# VM_Motor_v2_3.net
KiCad netlist of a schematic drawn in EAGLE
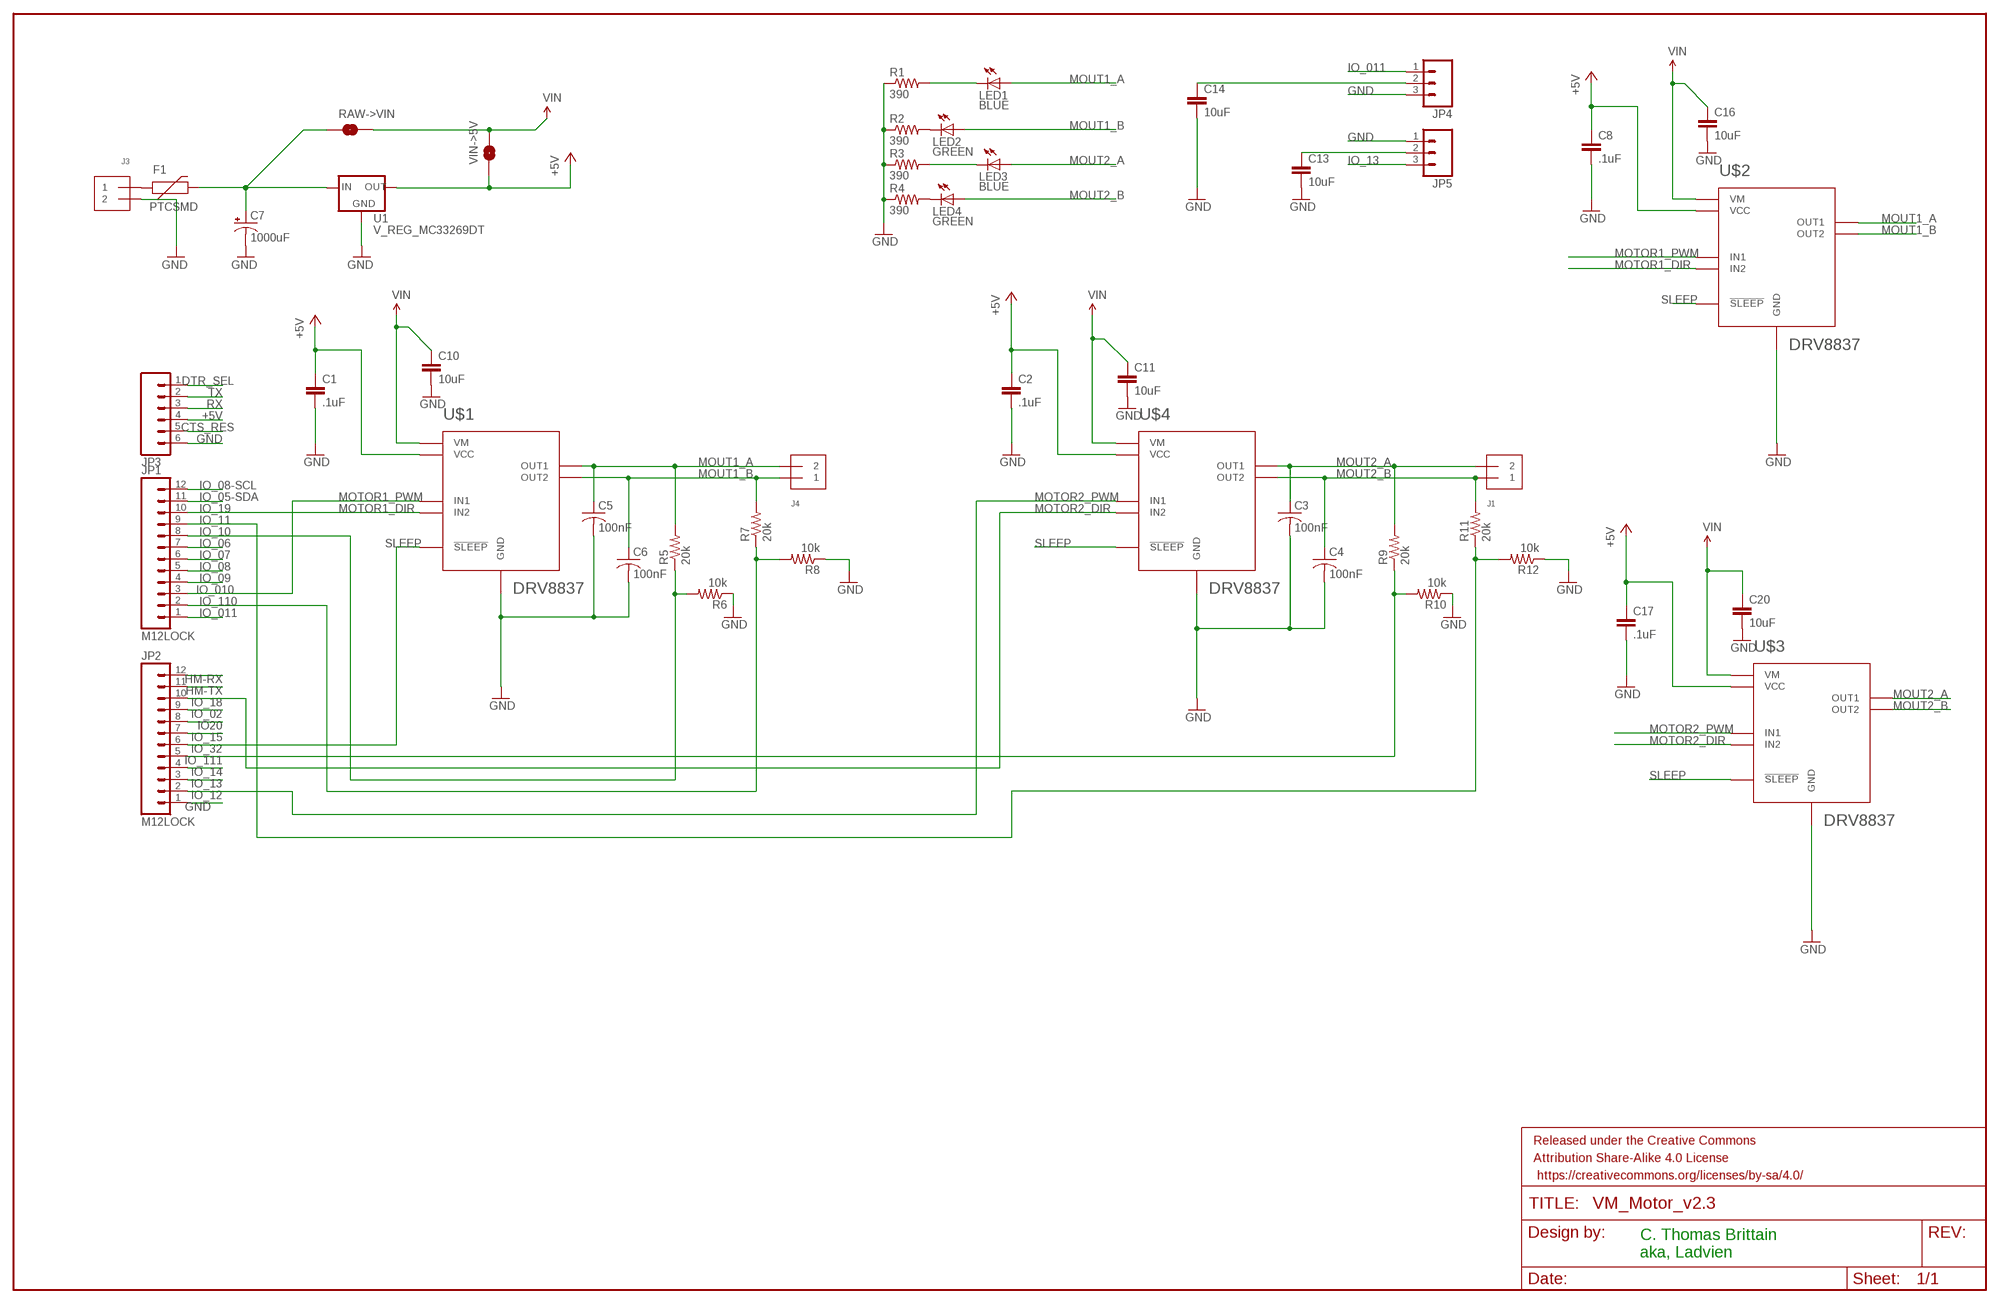
[diagram p0: schematic, sheet 1]

(export (version "E")
  (design (tool "Eeschema 10.0.6"))
  (components
    (comp (ref "C1")
      (value ".1uF")
      (footprint "eagle-import:0402-CAP")
      (libsource (lib "eagle-import") (part "CAP0402-CAP"))
    )
    (comp (ref "C2")
      (value ".1uF")
      (footprint "eagle-import:0402-CAP")
      (libsource (lib "eagle-import") (part "CAP0402-CAP"))
    )
    (comp (ref "C3")
      (value "100nF")
      (footprint "eagle-import:C0402")
      (libsource (lib "eagle-import") (part "C-USC0402"))
    )
    (comp (ref "C4")
      (value "100nF")
      (footprint "eagle-import:C0402")
      (libsource (lib "eagle-import") (part "C-USC0402"))
    )
    (comp (ref "C5")
      (value "100nF")
      (footprint "eagle-import:C0402")
      (libsource (lib "eagle-import") (part "C-USC0402"))
    )
    (comp (ref "C6")
      (value "100nF")
      (footprint "eagle-import:C0402")
      (libsource (lib "eagle-import") (part "C-USC0402"))
    )
    (comp (ref "C7")
      (value "1000uF")
      (footprint "eagle-import:150CLZ-0810")
      (libsource (lib "eagle-import") (part "CPOL-US150CLZ-0810"))
    )
    (comp (ref "C8")
      (value ".1uF")
      (footprint "eagle-import:0402-CAP")
      (libsource (lib "eagle-import") (part "CAP0402-CAP"))
    )
    (comp (ref "C10")
      (value "10uF")
      (footprint "eagle-import:0402-CAP")
      (libsource (lib "eagle-import") (part "CAP0402-CAP"))
    )
    (comp (ref "C11")
      (value "10uF")
      (footprint "eagle-import:0402-CAP")
      (libsource (lib "eagle-import") (part "CAP0402-CAP"))
    )
    (comp (ref "C13")
      (value "10uF")
      (footprint "eagle-import:0402-CAP")
      (libsource (lib "eagle-import") (part "CAP0402-CAP"))
    )
    (comp (ref "C14")
      (value "10uF")
      (footprint "eagle-import:0402-CAP")
      (libsource (lib "eagle-import") (part "CAP0402-CAP"))
    )
    (comp (ref "C16")
      (value "10uF")
      (footprint "eagle-import:0402-CAP")
      (libsource (lib "eagle-import") (part "CAP0402-CAP"))
    )
    (comp (ref "C17")
      (value ".1uF")
      (footprint "eagle-import:0402-CAP")
      (libsource (lib "eagle-import") (part "CAP0402-CAP"))
    )
    (comp (ref "C20")
      (value "10uF")
      (footprint "eagle-import:0402-CAP")
      (libsource (lib "eagle-import") (part "CAP0402-CAP"))
    )
    (comp (ref "F1")
      (value "PTCSMD")
      (footprint "eagle-import:PTC-1206")
      (libsource (lib "eagle-import") (part "PTCSMD"))
    )
    (comp (ref "FRAME1")
      (value "FRAME-LEDGER")
      (footprint "eagle-import:CREATIVE_COMMONS")
      (libsource (lib "eagle-import") (part "FRAME-LEDGER"))
    )
    (comp (ref "J1")
      (value "TERMBLOCK_1X2")
      (footprint "eagle-import:TERMBLOCK_1X2-3.5MM")
      (libsource (lib "eagle-import") (part "TERMBLOCK_1X2"))
    )
    (comp (ref "J3")
      (value "TERMBLOCK_1X2")
      (footprint "eagle-import:TERMBLOCK_1X2-3.5MM")
      (libsource (lib "eagle-import") (part "TERMBLOCK_1X2"))
    )
    (comp (ref "J4")
      (value "TERMBLOCK_1X2")
      (footprint "eagle-import:TERMBLOCK_1X2-3.5MM")
      (libsource (lib "eagle-import") (part "TERMBLOCK_1X2"))
    )
    (comp (ref "JP1")
      (value "M12LOCK")
      (footprint "eagle-import:1X12_LOCK")
      (libsource (lib "eagle-import") (part "M12LOCK"))
    )
    (comp (ref "JP2")
      (value "M12LOCK")
      (footprint "eagle-import:1X12_LOCK")
      (libsource (lib "eagle-import") (part "M12LOCK"))
    )
    (comp (ref "JP3")
      (value "M06LOCK")
      (footprint "eagle-import:1X06_LOCK")
      (libsource (lib "eagle-import") (part "M06LOCK"))
    )
    (comp (ref "JP4")
      (value "M03LOCK")
      (footprint "eagle-import:1X03_LOCK")
      (libsource (lib "eagle-import") (part "M03LOCK"))
    )
    (comp (ref "JP5")
      (value "M03LOCK")
      (footprint "eagle-import:1X03_LOCK")
      (libsource (lib "eagle-import") (part "M03LOCK"))
    )
    (comp (ref "LED1")
      (value "BLUE")
      (footprint "eagle-import:CHIP-LED0603")
      (libsource (lib "eagle-import") (part "LEDCHIP-LED0603"))
    )
    (comp (ref "LED2")
      (value "GREEN")
      (footprint "eagle-import:CHIP-LED0603")
      (libsource (lib "eagle-import") (part "LEDCHIP-LED0603"))
    )
    (comp (ref "LED3")
      (value "BLUE")
      (footprint "eagle-import:CHIP-LED0603")
      (libsource (lib "eagle-import") (part "LEDCHIP-LED0603"))
    )
    (comp (ref "LED4")
      (value "GREEN")
      (footprint "eagle-import:CHIP-LED0603")
      (libsource (lib "eagle-import") (part "LEDCHIP-LED0603"))
    )
    (comp (ref "R1")
      (value "390")
      (footprint "eagle-import:R0402")
      (libsource (lib "eagle-import") (part "R-US_R0402"))
    )
    (comp (ref "R2")
      (value "390")
      (footprint "eagle-import:R0402")
      (libsource (lib "eagle-import") (part "R-US_R0402"))
    )
    (comp (ref "R3")
      (value "390")
      (footprint "eagle-import:R0402")
      (libsource (lib "eagle-import") (part "R-US_R0402"))
    )
    (comp (ref "R4")
      (value "390")
      (footprint "eagle-import:R0402")
      (libsource (lib "eagle-import") (part "R-US_R0402"))
    )
    (comp (ref "R5")
      (value "20k")
      (footprint "eagle-import:R0402")
      (libsource (lib "eagle-import") (part "R-US_R0402"))
    )
    (comp (ref "R6")
      (value "10k")
      (footprint "eagle-import:R0402")
      (libsource (lib "eagle-import") (part "R-US_R0402"))
    )
    (comp (ref "R7")
      (value "20k")
      (footprint "eagle-import:R0402")
      (libsource (lib "eagle-import") (part "R-US_R0402"))
    )
    (comp (ref "R8")
      (value "10k")
      (footprint "eagle-import:R0402")
      (libsource (lib "eagle-import") (part "R-US_R0402"))
    )
    (comp (ref "R9")
      (value "20k")
      (footprint "eagle-import:R0402")
      (libsource (lib "eagle-import") (part "R-US_R0402"))
    )
    (comp (ref "R10")
      (value "10k")
      (footprint "eagle-import:R0402")
      (libsource (lib "eagle-import") (part "R-US_R0402"))
    )
    (comp (ref "R11")
      (value "20k")
      (footprint "eagle-import:R0402")
      (libsource (lib "eagle-import") (part "R-US_R0402"))
    )
    (comp (ref "R12")
      (value "10k")
      (footprint "eagle-import:R0402")
      (libsource (lib "eagle-import") (part "R-US_R0402"))
    )
    (comp (ref "RAW->VIN")
      (value "SOLDERJUMPERNO")
      (footprint "eagle-import:SJ_2S-NO")
      (libsource (lib "eagle-import") (part "SOLDERJUMPERNO"))
    )
    (comp (ref "U$1")
      (value "DRV8837")
      (footprint "eagle-import:QFN8")
      (libsource (lib "eagle-import") (part "DRV8837"))
    )
    (comp (ref "U$2")
      (value "DRV8837")
      (footprint "eagle-import:QFN8")
      (libsource (lib "eagle-import") (part "DRV8837"))
    )
    (comp (ref "U$3")
      (value "DRV8837")
      (footprint "eagle-import:QFN8")
      (libsource (lib "eagle-import") (part "DRV8837"))
    )
    (comp (ref "U$4")
      (value "DRV8837")
      (footprint "eagle-import:QFN8")
      (libsource (lib "eagle-import") (part "DRV8837"))
    )
    (comp (ref "U1")
      (value "V_REG_MC33269DT")
      (footprint "eagle-import:DPAK")
      (libsource (lib "eagle-import") (part "V_REG_MC33269DT"))
    )
    (comp (ref "VIN->5V")
      (value "SOLDERJUMPERNO")
      (footprint "eagle-import:SJ_2S-NO")
      (libsource (lib "eagle-import") (part "SOLDERJUMPERNO"))
    )
  )
  (nets
    (net (code "1") (name "+5V") (class "Default")
      (node (ref "C1") (pin "1") (pinfunction "1_1") (pintype "passive"))
      (node (ref "C13") (pin "1") (pinfunction "1_1") (pintype "passive"))
      (node (ref "C14") (pin "1") (pinfunction "1_1") (pintype "passive"))
      (node (ref "C17") (pin "1") (pinfunction "1_1") (pintype "passive"))
      (node (ref "C2") (pin "1") (pinfunction "1_1") (pintype "passive"))
      (node (ref "C8") (pin "1") (pinfunction "1_1") (pintype "passive"))
      (node (ref "JP3") (pin "4") (pinfunction "4_4") (pintype "passive"))
      (node (ref "JP4") (pin "2") (pinfunction "2_2") (pintype "passive"))
      (node (ref "JP5") (pin "2") (pinfunction "2_2") (pintype "passive"))
      (node (ref "U$1") (pin "P$8") (pinfunction "VCC_P$8") (pintype "bidirectional"))
      (node (ref "U$2") (pin "P$8") (pinfunction "VCC_P$8") (pintype "bidirectional"))
      (node (ref "U$3") (pin "P$8") (pinfunction "VCC_P$8") (pintype "bidirectional"))
      (node (ref "U$4") (pin "P$8") (pinfunction "VCC_P$8") (pintype "bidirectional"))
      (node (ref "U1") (pin "4") (pinfunction "OUT_4") (pintype "output"))
      (node (ref "VIN->5V") (pin "1") (pinfunction "1_1") (pintype "passive"))
    )
    (net (code "2") (name "/CTS_RES") (class "Default")
      (node (ref "JP3") (pin "5") (pinfunction "5_5") (pintype "passive"))
    )
    (net (code "3") (name "/DTR_SEL") (class "Default")
      (node (ref "JP3") (pin "1") (pinfunction "1_1") (pintype "passive"))
    )
    (net (code "4") (name "/HM-RX") (class "Default")
      (node (ref "JP2") (pin "12") (pinfunction "12_12") (pintype "passive"))
    )
    (net (code "5") (name "/HM-TX") (class "Default")
      (node (ref "JP2") (pin "11") (pinfunction "11_11") (pintype "passive"))
    )
    (net (code "6") (name "/IO20") (class "Default")
      (node (ref "JP2") (pin "8") (pinfunction "8_8") (pintype "passive"))
    )
    (net (code "7") (name "/IO_02") (class "Default")
      (node (ref "JP2") (pin "9") (pinfunction "9_9") (pintype "passive"))
    )
    (net (code "8") (name "/IO_05-SDA") (class "Default")
      (node (ref "JP1") (pin "11") (pinfunction "11_11") (pintype "passive"))
    )
    (net (code "9") (name "/IO_06") (class "Default")
      (node (ref "JP1") (pin "7") (pinfunction "7_7") (pintype "passive"))
    )
    (net (code "10") (name "/IO_07") (class "Default")
      (node (ref "JP1") (pin "6") (pinfunction "6_6") (pintype "passive"))
    )
    (net (code "11") (name "/IO_08") (class "Default")
      (node (ref "JP1") (pin "5") (pinfunction "5_5") (pintype "passive"))
    )
    (net (code "12") (name "/IO_08-SCL") (class "Default")
      (node (ref "JP1") (pin "12") (pinfunction "12_12") (pintype "passive"))
    )
    (net (code "13") (name "/IO_09") (class "Default")
      (node (ref "JP1") (pin "4") (pinfunction "4_4") (pintype "passive"))
    )
    (net (code "14") (name "/IO_10") (class "Default")
      (node (ref "JP1") (pin "8") (pinfunction "8_8") (pintype "passive"))
      (node (ref "R5") (pin "1") (pinfunction "1_1") (pintype "passive"))
      (node (ref "R6") (pin "2") (pinfunction "2_2") (pintype "passive"))
    )
    (net (code "15") (name "/IO_011") (class "Default")
      (node (ref "JP1") (pin "1") (pinfunction "1_1") (pintype "passive"))
      (node (ref "JP4") (pin "1") (pinfunction "1_1") (pintype "passive"))
    )
    (net (code "16") (name "/IO_13") (class "Default")
      (node (ref "JP2") (pin "3") (pinfunction "3_3") (pintype "passive"))
      (node (ref "JP5") (pin "3") (pinfunction "3_3") (pintype "passive"))
    )
    (net (code "17") (name "/IO_14") (class "Default")
      (node (ref "JP2") (pin "4") (pinfunction "4_4") (pintype "passive"))
    )
    (net (code "18") (name "/IO_15") (class "Default")
      (node (ref "JP2") (pin "7") (pinfunction "7_7") (pintype "passive"))
    )
    (net (code "19") (name "/IO_110") (class "Default")
      (node (ref "JP1") (pin "2") (pinfunction "2_2") (pintype "passive"))
      (node (ref "R7") (pin "1") (pinfunction "1_1") (pintype "passive"))
      (node (ref "R8") (pin "2") (pinfunction "2_2") (pintype "passive"))
    )
    (net (code "20") (name "/IO_111") (class "Default")
      (node (ref "JP2") (pin "5") (pinfunction "5_5") (pintype "passive"))
      (node (ref "R10") (pin "2") (pinfunction "2_2") (pintype "passive"))
      (node (ref "R9") (pin "1") (pinfunction "1_1") (pintype "passive"))
    )
    (net (code "21") (name "/MOTOR1_DIR") (class "Default")
      (node (ref "JP1") (pin "10") (pinfunction "10_10") (pintype "passive"))
      (node (ref "U$1") (pin "P$5") (pinfunction "IN2_P$5") (pintype "bidirectional"))
      (node (ref "U$2") (pin "P$5") (pinfunction "IN2_P$5") (pintype "bidirectional"))
    )
    (net (code "22") (name "/MOTOR1_PWM") (class "Default")
      (node (ref "JP1") (pin "3") (pinfunction "3_3") (pintype "passive"))
      (node (ref "U$1") (pin "P$6") (pinfunction "IN1_P$6") (pintype "bidirectional"))
      (node (ref "U$2") (pin "P$6") (pinfunction "IN1_P$6") (pintype "bidirectional"))
    )
    (net (code "23") (name "/MOTOR2_DIR") (class "Default")
      (node (ref "JP2") (pin "10") (pinfunction "10_10") (pintype "passive"))
      (node (ref "U$3") (pin "P$5") (pinfunction "IN2_P$5") (pintype "bidirectional"))
      (node (ref "U$4") (pin "P$5") (pinfunction "IN2_P$5") (pintype "bidirectional"))
    )
    (net (code "24") (name "/MOTOR2_PWM") (class "Default")
      (node (ref "JP2") (pin "2") (pinfunction "2_2") (pintype "passive"))
      (node (ref "U$3") (pin "P$6") (pinfunction "IN1_P$6") (pintype "bidirectional"))
      (node (ref "U$4") (pin "P$6") (pinfunction "IN1_P$6") (pintype "bidirectional"))
    )
    (net (code "25") (name "/MOUT1_A") (class "Default")
      (node (ref "C5") (pin "1") (pinfunction "1_1") (pintype "passive"))
      (node (ref "J4") (pin "2") (pinfunction "2_2") (pintype "passive"))
      (node (ref "LED1") (pin "A") (pinfunction "A_A") (pintype "passive"))
      (node (ref "R5") (pin "2") (pinfunction "2_2") (pintype "passive"))
      (node (ref "U$1") (pin "P$2") (pinfunction "OUT1_P$2") (pintype "bidirectional"))
      (node (ref "U$2") (pin "P$2") (pinfunction "OUT1_P$2") (pintype "bidirectional"))
    )
    (net (code "26") (name "/MOUT1_B") (class "Default")
      (node (ref "C6") (pin "1") (pinfunction "1_1") (pintype "passive"))
      (node (ref "J4") (pin "1") (pinfunction "1_1") (pintype "passive"))
      (node (ref "LED2") (pin "A") (pinfunction "A_A") (pintype "passive"))
      (node (ref "R7") (pin "2") (pinfunction "2_2") (pintype "passive"))
      (node (ref "U$1") (pin "P$3") (pinfunction "OUT2_P$3") (pintype "bidirectional"))
      (node (ref "U$2") (pin "P$3") (pinfunction "OUT2_P$3") (pintype "bidirectional"))
    )
    (net (code "27") (name "/MOUT2_A") (class "Default")
      (node (ref "C3") (pin "1") (pinfunction "1_1") (pintype "passive"))
      (node (ref "J1") (pin "2") (pinfunction "2_2") (pintype "passive"))
      (node (ref "LED3") (pin "A") (pinfunction "A_A") (pintype "passive"))
      (node (ref "R9") (pin "2") (pinfunction "2_2") (pintype "passive"))
      (node (ref "U$3") (pin "P$2") (pinfunction "OUT1_P$2") (pintype "bidirectional"))
      (node (ref "U$4") (pin "P$2") (pinfunction "OUT1_P$2") (pintype "bidirectional"))
    )
    (net (code "28") (name "/MOUT2_B") (class "Default")
      (node (ref "C4") (pin "1") (pinfunction "1_1") (pintype "passive"))
      (node (ref "J1") (pin "1") (pinfunction "1_1") (pintype "passive"))
      (node (ref "LED4") (pin "A") (pinfunction "A_A") (pintype "passive"))
      (node (ref "R11") (pin "2") (pinfunction "2_2") (pintype "passive"))
      (node (ref "U$3") (pin "P$3") (pinfunction "OUT2_P$3") (pintype "bidirectional"))
      (node (ref "U$4") (pin "P$3") (pinfunction "OUT2_P$3") (pintype "bidirectional"))
    )
    (net (code "29") (name "/RX") (class "Default")
      (node (ref "JP3") (pin "3") (pinfunction "3_3") (pintype "passive"))
    )
    (net (code "30") (name "/SLEEP") (class "Default")
      (node (ref "JP2") (pin "6") (pinfunction "6_6") (pintype "passive"))
      (node (ref "U$1") (pin "P$7") (pinfunction "~{SLEEP}_P$7") (pintype "bidirectional"))
      (node (ref "U$2") (pin "P$7") (pinfunction "~{SLEEP}_P$7") (pintype "bidirectional"))
      (node (ref "U$3") (pin "P$7") (pinfunction "~{SLEEP}_P$7") (pintype "bidirectional"))
      (node (ref "U$4") (pin "P$7") (pinfunction "~{SLEEP}_P$7") (pintype "bidirectional"))
    )
    (net (code "31") (name "/TX") (class "Default")
      (node (ref "JP3") (pin "2") (pinfunction "2_2") (pintype "passive"))
    )
    (net (code "32") (name "GND") (class "Default")
      (node (ref "C1") (pin "2") (pinfunction "2_2") (pintype "passive"))
      (node (ref "C10") (pin "2") (pinfunction "2_2") (pintype "passive"))
      (node (ref "C11") (pin "2") (pinfunction "2_2") (pintype "passive"))
      (node (ref "C13") (pin "2") (pinfunction "2_2") (pintype "passive"))
      (node (ref "C14") (pin "2") (pinfunction "2_2") (pintype "passive"))
      (node (ref "C16") (pin "2") (pinfunction "2_2") (pintype "passive"))
      (node (ref "C17") (pin "2") (pinfunction "2_2") (pintype "passive"))
      (node (ref "C2") (pin "2") (pinfunction "2_2") (pintype "passive"))
      (node (ref "C20") (pin "2") (pinfunction "2_2") (pintype "passive"))
      (node (ref "C3") (pin "2") (pinfunction "2_2") (pintype "passive"))
      (node (ref "C4") (pin "2") (pinfunction "2_2") (pintype "passive"))
      (node (ref "C5") (pin "2") (pinfunction "2_2") (pintype "passive"))
      (node (ref "C6") (pin "2") (pinfunction "2_2") (pintype "passive"))
      (node (ref "C7") (pin "-") (pinfunction "-_-") (pintype "passive"))
      (node (ref "C8") (pin "2") (pinfunction "2_2") (pintype "passive"))
      (node (ref "J3") (pin "2") (pinfunction "2_2") (pintype "passive"))
      (node (ref "JP2") (pin "1") (pinfunction "1_1") (pintype "passive"))
      (node (ref "JP3") (pin "6") (pinfunction "6_6") (pintype "passive"))
      (node (ref "JP4") (pin "3") (pinfunction "3_3") (pintype "passive"))
      (node (ref "JP5") (pin "1") (pinfunction "1_1") (pintype "passive"))
      (node (ref "R1") (pin "1") (pinfunction "1_1") (pintype "passive"))
      (node (ref "R10") (pin "1") (pinfunction "1_1") (pintype "passive"))
      (node (ref "R12") (pin "1") (pinfunction "1_1") (pintype "passive"))
      (node (ref "R2") (pin "1") (pinfunction "1_1") (pintype "passive"))
      (node (ref "R3") (pin "1") (pinfunction "1_1") (pintype "passive"))
      (node (ref "R4") (pin "1") (pinfunction "1_1") (pintype "passive"))
      (node (ref "R6") (pin "1") (pinfunction "1_1") (pintype "passive"))
      (node (ref "R8") (pin "1") (pinfunction "1_1") (pintype "passive"))
      (node (ref "U$1") (pin "P$10") (pinfunction "GND_P$10") (pintype "bidirectional"))
      (node (ref "U$1") (pin "P$11") (pinfunction "GND_P$11") (pintype "bidirectional"))
      (node (ref "U$1") (pin "P$4") (pinfunction "GND_P$4") (pintype "bidirectional"))
      (node (ref "U$1") (pin "P$9") (pinfunction "GND_P$9") (pintype "bidirectional"))
      (node (ref "U$2") (pin "P$10") (pinfunction "GND_P$10") (pintype "bidirectional"))
      (node (ref "U$2") (pin "P$11") (pinfunction "GND_P$11") (pintype "bidirectional"))
      (node (ref "U$2") (pin "P$4") (pinfunction "GND_P$4") (pintype "bidirectional"))
      (node (ref "U$2") (pin "P$9") (pinfunction "GND_P$9") (pintype "bidirectional"))
      (node (ref "U$3") (pin "P$10") (pinfunction "GND_P$10") (pintype "bidirectional"))
      (node (ref "U$3") (pin "P$11") (pinfunction "GND_P$11") (pintype "bidirectional"))
      (node (ref "U$3") (pin "P$4") (pinfunction "GND_P$4") (pintype "bidirectional"))
      (node (ref "U$3") (pin "P$9") (pinfunction "GND_P$9") (pintype "bidirectional"))
      (node (ref "U$4") (pin "P$10") (pinfunction "GND_P$10") (pintype "bidirectional"))
      (node (ref "U$4") (pin "P$11") (pinfunction "GND_P$11") (pintype "bidirectional"))
      (node (ref "U$4") (pin "P$4") (pinfunction "GND_P$4") (pintype "bidirectional"))
      (node (ref "U$4") (pin "P$9") (pinfunction "GND_P$9") (pintype "bidirectional"))
      (node (ref "U1") (pin "1") (pinfunction "GND_1") (pintype "input"))
    )
    (net (code "33") (name "Net-(F1-Pad1)") (class "Default")
      (node (ref "F1") (pin "1") (pinfunction "1_1") (pintype "bidirectional"))
      (node (ref "J3") (pin "1") (pinfunction "1_1") (pintype "passive"))
    )
    (net (code "34") (name "Net-(JP1-Pad9)") (class "Default")
      (node (ref "JP1") (pin "9") (pinfunction "9_9") (pintype "passive"))
      (node (ref "R11") (pin "1") (pinfunction "1_1") (pintype "passive"))
      (node (ref "R12") (pin "2") (pinfunction "2_2") (pintype "passive"))
    )
    (net (code "35") (name "Net-(LED1-PadC)") (class "Default")
      (node (ref "LED1") (pin "C") (pinfunction "C_C") (pintype "passive"))
      (node (ref "R1") (pin "2") (pinfunction "2_2") (pintype "passive"))
    )
    (net (code "36") (name "Net-(LED2-PadC)") (class "Default")
      (node (ref "LED2") (pin "C") (pinfunction "C_C") (pintype "passive"))
      (node (ref "R2") (pin "2") (pinfunction "2_2") (pintype "passive"))
    )
    (net (code "37") (name "Net-(LED3-PadC)") (class "Default")
      (node (ref "LED3") (pin "C") (pinfunction "C_C") (pintype "passive"))
      (node (ref "R3") (pin "2") (pinfunction "2_2") (pintype "passive"))
    )
    (net (code "38") (name "Net-(LED4-PadC)") (class "Default")
      (node (ref "LED4") (pin "C") (pinfunction "C_C") (pintype "passive"))
      (node (ref "R4") (pin "2") (pinfunction "2_2") (pintype "passive"))
    )
    (net (code "39") (name "Net-(U1-IN)") (class "Default")
      (node (ref "C7") (pin "+") (pinfunction "+_+") (pintype "passive"))
      (node (ref "F1") (pin "2") (pinfunction "2_2") (pintype "bidirectional"))
      (node (ref "RAW->VIN") (pin "1") (pinfunction "1_1") (pintype "passive"))
      (node (ref "U1") (pin "3") (pinfunction "IN_3") (pintype "input"))
    )
    (net (code "40") (name "VIN") (class "Default")
      (node (ref "C10") (pin "1") (pinfunction "1_1") (pintype "passive"))
      (node (ref "C11") (pin "1") (pinfunction "1_1") (pintype "passive"))
      (node (ref "C16") (pin "1") (pinfunction "1_1") (pintype "passive"))
      (node (ref "C20") (pin "1") (pinfunction "1_1") (pintype "passive"))
      (node (ref "RAW->VIN") (pin "2") (pinfunction "2_2") (pintype "passive"))
      (node (ref "U$1") (pin "P$1") (pinfunction "VM_P$1") (pintype "bidirectional"))
      (node (ref "U$2") (pin "P$1") (pinfunction "VM_P$1") (pintype "bidirectional"))
      (node (ref "U$3") (pin "P$1") (pinfunction "VM_P$1") (pintype "bidirectional"))
      (node (ref "U$4") (pin "P$1") (pinfunction "VM_P$1") (pintype "bidirectional"))
      (node (ref "VIN->5V") (pin "2") (pinfunction "2_2") (pintype "passive"))
    )
  )
)
